# LCD_Power.net
KiCad netlist of a schematic drawn in Altium Designer
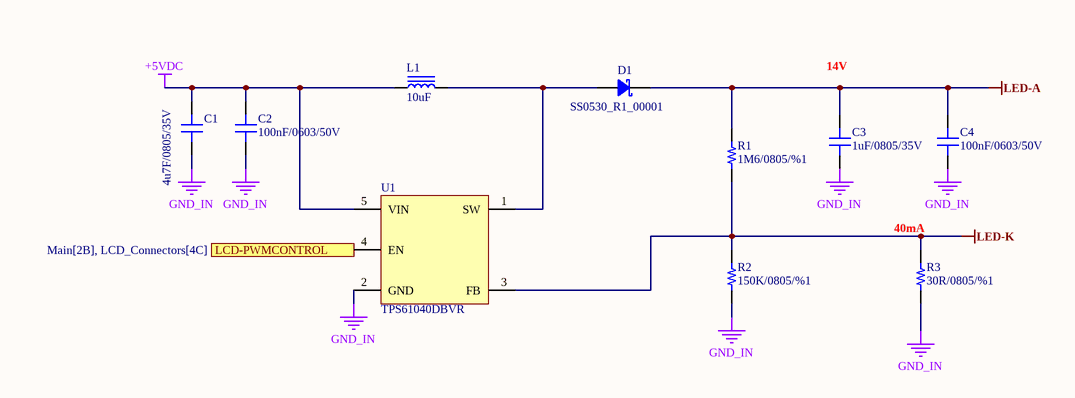
[diagram p0: LCD_Power.SchDoc]

(export (version "E")
  (design (tool "Eeschema 10.0.6"))
  (components
    (comp (ref "C1")
      (value "4u7F/0805/35V")
      (footprint "0805_cap")
      (libsource (lib "IM_v1.0") (part "Capacitor"))
    )
    (comp (ref "C2")
      (value "100nF/0603/50V")
      (footprint "0603_cap")
      (libsource (lib "IM_v1.0") (part "Capacitor"))
    )
    (comp (ref "C3")
      (value "1uF/0805/35V")
      (footprint "0603_cap")
      (libsource (lib "IM_v1.0") (part "Capacitor"))
    )
    (comp (ref "C4")
      (value "100nF/0603/50V")
      (footprint "0603_cap")
      (libsource (lib "IM_v1.0") (part "Capacitor"))
    )
    (comp (ref "D1")
      (value "SS0530_R1_00001")
      (footprint "SOD-123")
      (libsource (lib "IM_v1.0") (part "SCHOTKY DIODE"))
    )
    (comp (ref "L1")
      (value "10uF")
      (footprint "IND(4.5mmX4mm)")
      (description "CR32NP-100KC")
      (libsource (lib "IM_v1.0") (part "Inductor"))
    )
    (comp (ref "R1") (value "1M6/0805/%1") (footprint "0805_res") (libsource (lib "IM_v1.0") (part "RES")))
    (comp (ref "R2") (value "150K/0805/%1") (footprint "0805_res") (libsource (lib "IM_v1.0") (part "RES")))
    (comp (ref "R3") (value "30R/0805/%1") (footprint "0805_res") (libsource (lib "IM_v1.0") (part "RES")))
    (comp (ref "U1")
      (value "TPS61040DBVR")
      (footprint "SOT-23-5")
      (description "LED Driver IC 1 Output DC DC Regulator Step-Up (Boost) PWM Dimming 350mA (Switch) SOT-23-5")
      (fields (field (name "MANUFACTURER") "Texas Instruments"))
      (libsource (lib "IM_v1.0") (part "TPS61040DBVR"))
    )
  )
  (nets
    (net (code "1") (name "+5VDC") (class "Default")
      (node (ref "C1") (pin "2") (pinfunction "2_2") (pintype "passive"))
      (node (ref "C2") (pin "2") (pinfunction "2_2") (pintype "passive"))
      (node (ref "L1") (pin "1") (pinfunction "1_1") (pintype "passive"))
      (node (ref "U1") (pin "5") (pinfunction "VIN_5") (pintype "passive"))
    )
    (net (code "2") (name "/LCD-PWMCONTROL") (class "Default")
      (node (ref "U1") (pin "4") (pinfunction "EN_4") (pintype "passive"))
    )
    (net (code "3") (name "GND_IN") (class "Default")
      (node (ref "C1") (pin "1") (pinfunction "1_1") (pintype "passive"))
      (node (ref "C2") (pin "1") (pinfunction "1_1") (pintype "passive"))
      (node (ref "C3") (pin "1") (pinfunction "1_1") (pintype "passive"))
      (node (ref "C4") (pin "1") (pinfunction "1_1") (pintype "passive"))
      (node (ref "R2") (pin "1") (pinfunction "1_1") (pintype "passive"))
      (node (ref "R3") (pin "1") (pinfunction "1_1") (pintype "passive"))
      (node (ref "U1") (pin "2") (pinfunction "GND_2") (pintype "passive"))
    )
    (net (code "4") (name "LED-A") (class "Default")
      (node (ref "C3") (pin "2") (pinfunction "2_2") (pintype "passive"))
      (node (ref "C4") (pin "2") (pinfunction "2_2") (pintype "passive"))
      (node (ref "D1") (pin "1") (pinfunction "1_1") (pintype "passive"))
      (node (ref "R1") (pin "2") (pinfunction "2_2") (pintype "passive"))
    )
    (net (code "5") (name "LED-K") (class "Default")
      (node (ref "R1") (pin "1") (pinfunction "1_1") (pintype "passive"))
      (node (ref "R2") (pin "2") (pinfunction "2_2") (pintype "passive"))
      (node (ref "R3") (pin "2") (pinfunction "2_2") (pintype "passive"))
      (node (ref "U1") (pin "3") (pinfunction "FB_3") (pintype "passive"))
    )
    (net (code "6") (name "Net-(U1-SW)") (class "Default")
      (node (ref "D1") (pin "2") (pinfunction "2_2") (pintype "passive"))
      (node (ref "L1") (pin "2") (pinfunction "2_2") (pintype "passive"))
      (node (ref "U1") (pin "1") (pinfunction "SW_1") (pintype "passive"))
    )
  )
)
